# NSE2020_1.net
KiCad netlist of a schematic drawn in EAGLE
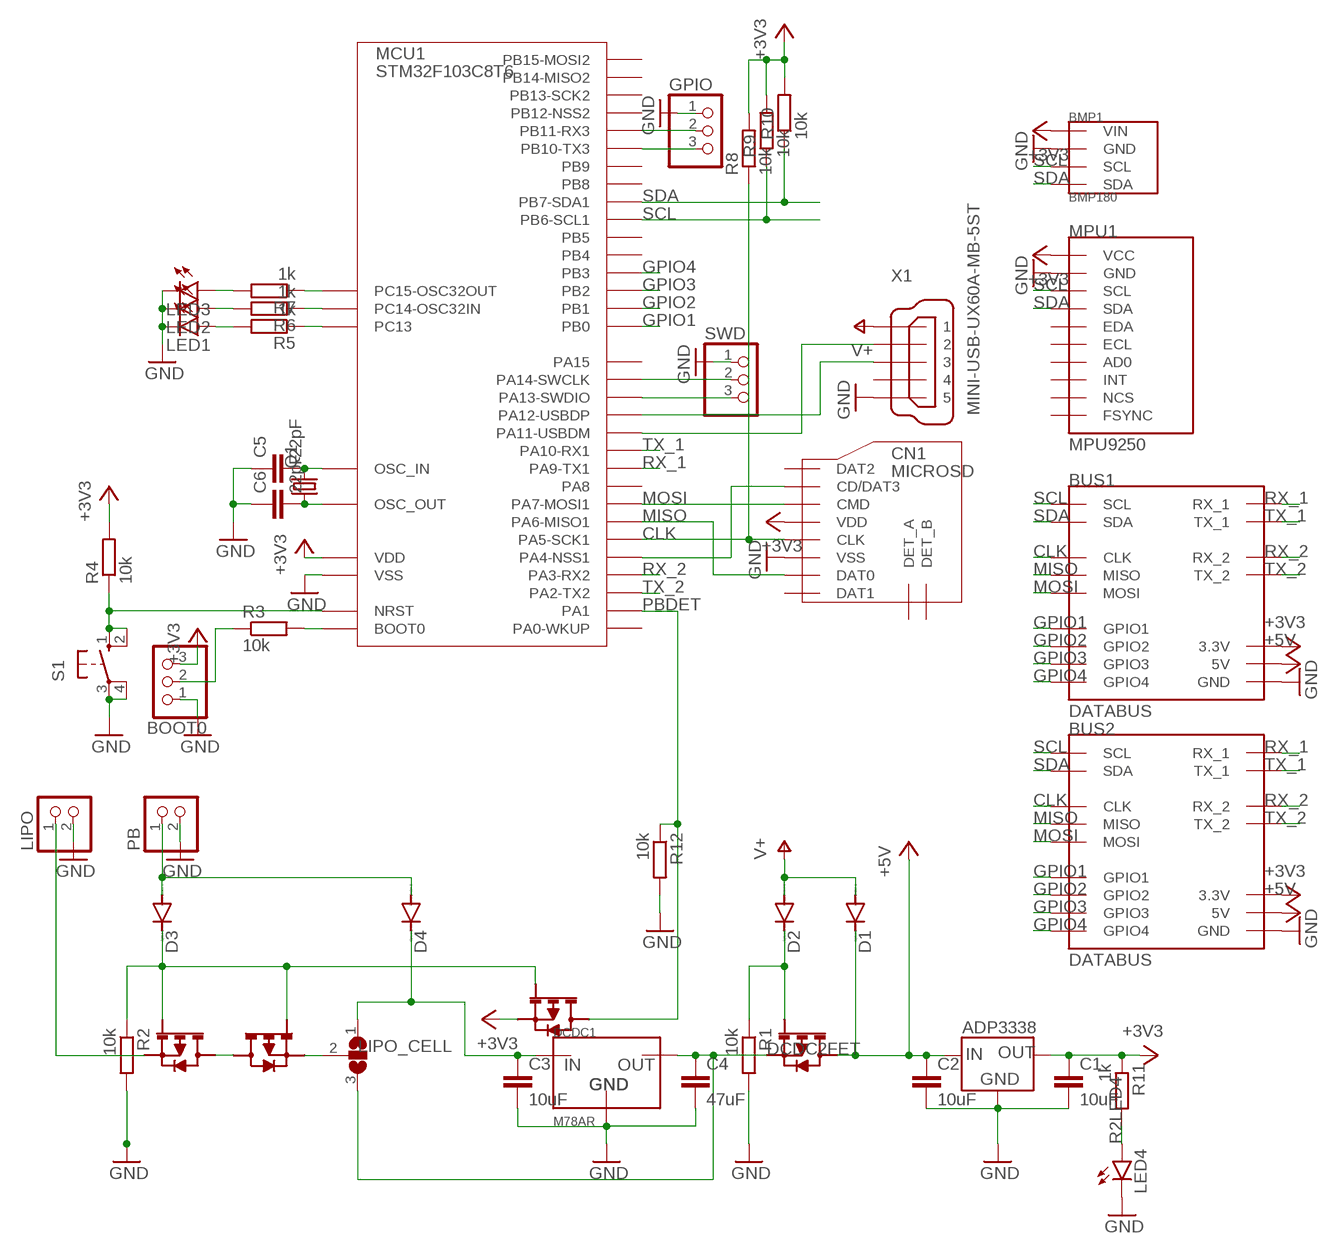
[diagram p0: schematic, sheet 1]

(export (version "E")
  (design (tool "Eeschema 10.0.6"))
  (components
    (comp (ref "BMP1")
      (value "BMP180")
      (footprint "eagle-import:GY-68")
      (libsource (lib "eagle-import") (part "BMP180"))
    )
    (comp (ref "BOOT0")
      (value "PINHD-1X3")
      (footprint "eagle-import:1X03")
      (libsource (lib "eagle-import") (part "PINHD-1X3"))
    )
    (comp (ref "BUS1")
      (value "DATABUS")
      (footprint "eagle-import:8X2")
      (libsource (lib "eagle-import") (part "DATABUS"))
    )
    (comp (ref "BUS2")
      (value "DATABUS")
      (footprint "eagle-import:8X2")
      (libsource (lib "eagle-import") (part "DATABUS"))
    )
    (comp (ref "C1")
      (value "10uF")
      (footprint "eagle-import:C2012")
      (libsource (lib "eagle-import") (part "C-EUC2012"))
    )
    (comp (ref "C2")
      (value "10uF")
      (footprint "eagle-import:C2012")
      (libsource (lib "eagle-import") (part "C-EUC2012"))
    )
    (comp (ref "C3")
      (value "10uF")
      (footprint "eagle-import:C2012")
      (libsource (lib "eagle-import") (part "C-EUC2012"))
    )
    (comp (ref "C4")
      (value "47uF")
      (footprint "eagle-import:C2012")
      (libsource (lib "eagle-import") (part "C-EUC2012"))
    )
    (comp (ref "C5")
      (value "22pF")
      (footprint "eagle-import:C2012")
      (libsource (lib "eagle-import") (part "C-EUC2012"))
    )
    (comp (ref "C6")
      (value "22pF")
      (footprint "eagle-import:C2012")
      (libsource (lib "eagle-import") (part "C-EUC2012"))
    )
    (comp (ref "CN1")
      (value "MICROSD")
      (footprint "eagle-import:DM3AT")
      (libsource (lib "eagle-import") (part "MICROSD"))
    )
    (comp (ref "D1")
      (value "DIODE-SOD123")
      (footprint "eagle-import:SOD123")
      (libsource (lib "eagle-import") (part "DIODE-SOD123"))
    )
    (comp (ref "D2")
      (value "DIODE-SOD123")
      (footprint "eagle-import:SOD123")
      (libsource (lib "eagle-import") (part "DIODE-SOD123"))
    )
    (comp (ref "D3")
      (value "DIODE-SOD123")
      (footprint "eagle-import:SOD123")
      (libsource (lib "eagle-import") (part "DIODE-SOD123"))
    )
    (comp (ref "D4")
      (value "DIODE-SOD123")
      (footprint "eagle-import:SOD123")
      (libsource (lib "eagle-import") (part "DIODE-SOD123"))
    )
    (comp (ref "DCDC1")
      (value "M78AR")
      (footprint "eagle-import:M78AR")
      (libsource (lib "eagle-import") (part "M78AR"))
    )
    (comp (ref "GPIO")
      (value "PINHD-1X3")
      (footprint "eagle-import:1X03")
      (libsource (lib "eagle-import") (part "PINHD-1X3"))
    )
    (comp (ref "IC1")
      (value "ADP3338-3.3")
      (footprint "eagle-import:SOT-223")
      (libsource (lib "eagle-import") (part "ADP3338-3.3"))
    )
    (comp (ref "LED1")
      (value "LEDSMT1206")
      (footprint "eagle-import:1206")
      (libsource (lib "eagle-import") (part "LEDSMT1206"))
    )
    (comp (ref "LED2")
      (value "LEDSMT1206")
      (footprint "eagle-import:1206")
      (libsource (lib "eagle-import") (part "LEDSMT1206"))
    )
    (comp (ref "LED3")
      (value "LEDSMT1206")
      (footprint "eagle-import:1206")
      (libsource (lib "eagle-import") (part "LEDSMT1206"))
    )
    (comp (ref "LED4")
      (value "LEDSMT1206")
      (footprint "eagle-import:1206")
      (libsource (lib "eagle-import") (part "LEDSMT1206"))
    )
    (comp (ref "LIPO")
      (value "PINHD-1X2")
      (footprint "eagle-import:1X02")
      (libsource (lib "eagle-import") (part "PINHD-1X2"))
    )
    (comp (ref "LIPO_CELL")
      (value "SJ2W")
      (footprint "eagle-import:SJ_2")
      (libsource (lib "eagle-import") (part "SJ2W"))
    )
    (comp (ref "MCU1")
      (value "STM32F103C8T6")
      (footprint "eagle-import:LQFP48")
      (libsource (lib "eagle-import") (part "STM32F103C8T6"))
    )
    (comp (ref "MPU1")
      (value "MPU9250")
      (footprint "eagle-import:GY-9250")
      (libsource (lib "eagle-import") (part "MPU9250"))
    )
    (comp (ref "PB")
      (value "PINHD-1X2")
      (footprint "eagle-import:1X02")
      (libsource (lib "eagle-import") (part "PINHD-1X2"))
    )
    (comp (ref "Q1")
      (value "CRYSTALHC49S")
      (footprint "eagle-import:HC49_S")
      (libsource (lib "eagle-import") (part "CRYSTALHC49S"))
    )
    (comp (ref "R1")
      (value "10k")
      (footprint "eagle-import:M2012")
      (libsource (lib "eagle-import") (part "R-EU_M2012"))
    )
    (comp (ref "R2")
      (value "10k")
      (footprint "eagle-import:M2012")
      (libsource (lib "eagle-import") (part "R-EU_M2012"))
    )
    (comp (ref "R3")
      (value "10k")
      (footprint "eagle-import:M2012")
      (libsource (lib "eagle-import") (part "R-EU_M2012"))
    )
    (comp (ref "R4")
      (value "10k")
      (footprint "eagle-import:M2012")
      (libsource (lib "eagle-import") (part "R-EU_M2012"))
    )
    (comp (ref "R5")
      (value "1k")
      (footprint "eagle-import:M2012")
      (libsource (lib "eagle-import") (part "R-EU_M2012"))
    )
    (comp (ref "R6")
      (value "1k")
      (footprint "eagle-import:M2012")
      (libsource (lib "eagle-import") (part "R-EU_M2012"))
    )
    (comp (ref "R7")
      (value "1k")
      (footprint "eagle-import:M2012")
      (libsource (lib "eagle-import") (part "R-EU_M2012"))
    )
    (comp (ref "R8")
      (value "10k")
      (footprint "eagle-import:M2012")
      (libsource (lib "eagle-import") (part "R-EU_M2012"))
    )
    (comp (ref "R9")
      (value "10k")
      (footprint "eagle-import:M2012")
      (libsource (lib "eagle-import") (part "R-EU_M2012"))
    )
    (comp (ref "R10")
      (value "10k")
      (footprint "eagle-import:M2012")
      (libsource (lib "eagle-import") (part "R-EU_M2012"))
    )
    (comp (ref "R11")
      (value "1k")
      (footprint "eagle-import:M2012")
      (libsource (lib "eagle-import") (part "R-EU_M2012"))
    )
    (comp (ref "R12")
      (value "10k")
      (footprint "eagle-import:M2012")
      (libsource (lib "eagle-import") (part "R-EU_M2012"))
    )
    (comp (ref "S1")
      (value "10-XX")
      (footprint "eagle-import:B3F-10XX")
      (fields (field (name "MPN") "B3F-1000"))
      (libsource (lib "eagle-import") (part "10-XX"))
    )
    (comp (ref "SWD")
      (value "PINHD-1X3")
      (footprint "eagle-import:1X03")
      (libsource (lib "eagle-import") (part "PINHD-1X3"))
    )
    (comp (ref "U$1")
      (value "2SJ681")
      (footprint "eagle-import:2SJ681")
      (libsource (lib "eagle-import") (part "2SJ681"))
    )
    (comp (ref "U$2")
      (value "2SJ681")
      (footprint "eagle-import:2SJ681")
      (libsource (lib "eagle-import") (part "2SJ681"))
    )
    (comp (ref "U$3")
      (value "2SJ681")
      (footprint "eagle-import:2SJ681")
      (libsource (lib "eagle-import") (part "2SJ681"))
    )
    (comp (ref "U$4")
      (value "2SJ681")
      (footprint "eagle-import:2SJ681")
      (libsource (lib "eagle-import") (part "2SJ681"))
    )
    (comp (ref "X1")
      (value "MINI-USB-UX60A-MB-5ST")
      (footprint "eagle-import:UX60A-MB-5ST")
      (libsource (lib "eagle-import") (part "MINI-USB-UX60A-MB-5ST"))
    )
  )
  (nets
    (net (code "1") (name "+3V3") (class "Default")
      (node (ref "BMP1") (pin "P1") (pinfunction "VIN_P1") (pintype "bidirectional"))
      (node (ref "BOOT0") (pin "3") (pinfunction "3_3") (pintype "passive"))
      (node (ref "BUS1") (pin "P6") (pinfunction "3.3V_P6") (pintype "bidirectional"))
      (node (ref "BUS2") (pin "P6") (pinfunction "3.3V_P6") (pintype "bidirectional"))
      (node (ref "C1") (pin "1") (pinfunction "1_1") (pintype "passive"))
      (node (ref "CN1") (pin "VDD") (pinfunction "VDD_VDD") (pintype "bidirectional"))
      (node (ref "IC1") (pin "1") (pinfunction "OUT_1") (pintype "output"))
      (node (ref "IC1") (pin "2") (pinfunction "OUT_2") (pintype "output"))
      (node (ref "MCU1") (pin "1") (pinfunction "VDD_1") (pintype "bidirectional"))
      (node (ref "MCU1") (pin "24") (pinfunction "VDD_24") (pintype "bidirectional"))
      (node (ref "MCU1") (pin "36") (pinfunction "VDD_36") (pintype "bidirectional"))
      (node (ref "MCU1") (pin "48") (pinfunction "VDD_48") (pintype "bidirectional"))
      (node (ref "MCU1") (pin "9") (pinfunction "VDD_9") (pintype "bidirectional"))
      (node (ref "MPU1") (pin "P1") (pinfunction "VCC_P1") (pintype "bidirectional"))
      (node (ref "R10") (pin "2") (pinfunction "2_2") (pintype "passive"))
      (node (ref "R11") (pin "1") (pinfunction "1_1") (pintype "passive"))
      (node (ref "R4") (pin "2") (pinfunction "2_2") (pintype "passive"))
      (node (ref "R8") (pin "2") (pinfunction "2_2") (pintype "passive"))
      (node (ref "R9") (pin "2") (pinfunction "2_2") (pintype "passive"))
      (node (ref "U$4") (pin "P$3") (pinfunction "P$3_P$3") (pintype "bidirectional"))
    )
    (net (code "2") (name "+5V") (class "Default")
      (node (ref "BUS1") (pin "P7") (pinfunction "5V_P7") (pintype "bidirectional"))
      (node (ref "BUS2") (pin "P7") (pinfunction "5V_P7") (pintype "bidirectional"))
      (node (ref "C2") (pin "1") (pinfunction "1_1") (pintype "passive"))
      (node (ref "D1") (pin "C") (pinfunction "C_C") (pintype "passive"))
      (node (ref "IC1") (pin "3") (pinfunction "IN_3") (pintype "input"))
      (node (ref "U$1") (pin "P$2") (pinfunction "P$1_P$2") (pintype "bidirectional"))
      (node (ref "U$1") (pin "P$4") (pinfunction "P$1_P$4") (pintype "bidirectional"))
    )
    (net (code "3") (name "/CLK") (class "Default")
      (node (ref "BUS1") (pin "P1") (pinfunction "CLK_P1") (pintype "bidirectional"))
      (node (ref "BUS2") (pin "P1") (pinfunction "CLK_P1") (pintype "bidirectional"))
      (node (ref "CN1") (pin "CLK") (pinfunction "CLK_CLK") (pintype "bidirectional"))
      (node (ref "MCU1") (pin "15") (pinfunction "PA5-SCK1_15") (pintype "bidirectional"))
      (node (ref "R8") (pin "1") (pinfunction "1_1") (pintype "passive"))
    )
    (net (code "4") (name "/DCDC2FET") (class "Default")
      (node (ref "C4") (pin "1") (pinfunction "1_1") (pintype "passive"))
      (node (ref "DCDC1") (pin "P3") (pinfunction "OUT_P3") (pintype "bidirectional"))
      (node (ref "LIPO_CELL") (pin "3") (pinfunction "3_3") (pintype "passive"))
      (node (ref "U$1") (pin "P$3") (pinfunction "P$3_P$3") (pintype "bidirectional"))
    )
    (net (code "5") (name "/GPIO1") (class "Default")
      (node (ref "BUS1") (pin "P3") (pinfunction "GPIO1_P3") (pintype "bidirectional"))
      (node (ref "BUS2") (pin "P3") (pinfunction "GPIO1_P3") (pintype "bidirectional"))
      (node (ref "MCU1") (pin "18") (pinfunction "PB0_18") (pintype "bidirectional"))
    )
    (net (code "6") (name "/GPIO2") (class "Default")
      (node (ref "BUS1") (pin "P10") (pinfunction "GPIO2_P10") (pintype "bidirectional"))
      (node (ref "BUS2") (pin "P10") (pinfunction "GPIO2_P10") (pintype "bidirectional"))
      (node (ref "MCU1") (pin "19") (pinfunction "PB1_19") (pintype "bidirectional"))
    )
    (net (code "7") (name "/GPIO3") (class "Default")
      (node (ref "BUS1") (pin "P14") (pinfunction "GPIO3_P14") (pintype "bidirectional"))
      (node (ref "BUS2") (pin "P14") (pinfunction "GPIO3_P14") (pintype "bidirectional"))
      (node (ref "MCU1") (pin "20") (pinfunction "PB2_20") (pintype "bidirectional"))
    )
    (net (code "8") (name "/GPIO4") (class "Default")
      (node (ref "BUS1") (pin "P15") (pinfunction "GPIO4_P15") (pintype "bidirectional"))
      (node (ref "BUS2") (pin "P15") (pinfunction "GPIO4_P15") (pintype "bidirectional"))
      (node (ref "MCU1") (pin "39") (pinfunction "PB3_39") (pintype "bidirectional"))
    )
    (net (code "9") (name "/MISO") (class "Default")
      (node (ref "BUS1") (pin "P12") (pinfunction "MISO_P12") (pintype "bidirectional"))
      (node (ref "BUS2") (pin "P12") (pinfunction "MISO_P12") (pintype "bidirectional"))
      (node (ref "CN1") (pin "DAT0") (pinfunction "DAT0_DAT0") (pintype "bidirectional"))
      (node (ref "MCU1") (pin "16") (pinfunction "PA6-MISO1_16") (pintype "bidirectional"))
    )
    (net (code "10") (name "/MOSI") (class "Default")
      (node (ref "BUS1") (pin "P2") (pinfunction "MOSI_P2") (pintype "bidirectional"))
      (node (ref "BUS2") (pin "P2") (pinfunction "MOSI_P2") (pintype "bidirectional"))
      (node (ref "CN1") (pin "CMD") (pinfunction "CMD_CMD") (pintype "bidirectional"))
      (node (ref "MCU1") (pin "17") (pinfunction "PA7-MOSI1_17") (pintype "bidirectional"))
    )
    (net (code "11") (name "/PBDET") (class "Default")
      (node (ref "MCU1") (pin "11") (pinfunction "PA1_11") (pintype "bidirectional"))
      (node (ref "R12") (pin "1") (pinfunction "1_1") (pintype "passive"))
      (node (ref "U$4") (pin "P$2") (pinfunction "P$1_P$2") (pintype "bidirectional"))
      (node (ref "U$4") (pin "P$4") (pinfunction "P$1_P$4") (pintype "bidirectional"))
    )
    (net (code "12") (name "/R2LED4") (class "Default")
      (node (ref "LED4") (pin "A") (pinfunction "A_A") (pintype "passive"))
      (node (ref "R11") (pin "2") (pinfunction "2_2") (pintype "passive"))
    )
    (net (code "13") (name "/RX_1") (class "Default")
      (node (ref "BUS1") (pin "P4") (pinfunction "RX_1_P4") (pintype "bidirectional"))
      (node (ref "BUS2") (pin "P4") (pinfunction "RX_1_P4") (pintype "bidirectional"))
      (node (ref "MCU1") (pin "30") (pinfunction "PA9-TX1_30") (pintype "bidirectional"))
    )
    (net (code "14") (name "/RX_2") (class "Default")
      (node (ref "BUS1") (pin "P9") (pinfunction "RX_2_P9") (pintype "bidirectional"))
      (node (ref "BUS2") (pin "P9") (pinfunction "RX_2_P9") (pintype "bidirectional"))
      (node (ref "MCU1") (pin "13") (pinfunction "PA3-RX2_13") (pintype "bidirectional"))
    )
    (net (code "15") (name "/SCL") (class "Default")
      (node (ref "BMP1") (pin "P3") (pinfunction "SCL_P3") (pintype "bidirectional"))
      (node (ref "BUS1") (pin "P0") (pinfunction "SCL_P0") (pintype "bidirectional"))
      (node (ref "BUS2") (pin "P0") (pinfunction "SCL_P0") (pintype "bidirectional"))
      (node (ref "MCU1") (pin "42") (pinfunction "PB6-SCL1_42") (pintype "bidirectional"))
      (node (ref "MPU1") (pin "P3") (pinfunction "SCL_P3") (pintype "bidirectional"))
      (node (ref "R9") (pin "1") (pinfunction "1_1") (pintype "passive"))
    )
    (net (code "16") (name "/SDA") (class "Default")
      (node (ref "BMP1") (pin "P4") (pinfunction "SDA_P4") (pintype "bidirectional"))
      (node (ref "BUS1") (pin "P13") (pinfunction "SDA_P13") (pintype "bidirectional"))
      (node (ref "BUS2") (pin "P13") (pinfunction "SDA_P13") (pintype "bidirectional"))
      (node (ref "MCU1") (pin "43") (pinfunction "PB7-SDA1_43") (pintype "bidirectional"))
      (node (ref "MPU1") (pin "P4") (pinfunction "SDA_P4") (pintype "bidirectional"))
      (node (ref "R10") (pin "1") (pinfunction "1_1") (pintype "passive"))
    )
    (net (code "17") (name "/TX_1") (class "Default")
      (node (ref "BUS1") (pin "P5") (pinfunction "TX_1_P5") (pintype "bidirectional"))
      (node (ref "BUS2") (pin "P5") (pinfunction "TX_1_P5") (pintype "bidirectional"))
      (node (ref "MCU1") (pin "31") (pinfunction "PA10-RX1_31") (pintype "bidirectional"))
    )
    (net (code "18") (name "/TX_2") (class "Default")
      (node (ref "BUS1") (pin "P8") (pinfunction "TX_2_P8") (pintype "bidirectional"))
      (node (ref "BUS2") (pin "P8") (pinfunction "TX_2_P8") (pintype "bidirectional"))
      (node (ref "MCU1") (pin "12") (pinfunction "PA2-TX2_12") (pintype "bidirectional"))
    )
    (net (code "19") (name "GND") (class "Default")
      (node (ref "BMP1") (pin "P2") (pinfunction "GND_P2") (pintype "bidirectional"))
      (node (ref "BOOT0") (pin "1") (pinfunction "1_1") (pintype "passive"))
      (node (ref "BUS1") (pin "P11") (pinfunction "GND_P11") (pintype "bidirectional"))
      (node (ref "BUS2") (pin "P11") (pinfunction "GND_P11") (pintype "bidirectional"))
      (node (ref "C1") (pin "2") (pinfunction "2_2") (pintype "passive"))
      (node (ref "C2") (pin "2") (pinfunction "2_2") (pintype "passive"))
      (node (ref "C3") (pin "2") (pinfunction "2_2") (pintype "passive"))
      (node (ref "C4") (pin "2") (pinfunction "2_2") (pintype "passive"))
      (node (ref "C5") (pin "1") (pinfunction "1_1") (pintype "passive"))
      (node (ref "C6") (pin "1") (pinfunction "1_1") (pintype "passive"))
      (node (ref "CN1") (pin "VSS") (pinfunction "VSS_VSS") (pintype "bidirectional"))
      (node (ref "DCDC1") (pin "P2") (pinfunction "GND_P2") (pintype "bidirectional"))
      (node (ref "GPIO") (pin "1") (pinfunction "1_1") (pintype "passive"))
      (node (ref "IC1") (pin "4") (pinfunction "GND_4") (pintype "bidirectional"))
      (node (ref "LED1") (pin "C") (pinfunction "C_C") (pintype "passive"))
      (node (ref "LED2") (pin "C") (pinfunction "C_C") (pintype "passive"))
      (node (ref "LED3") (pin "C") (pinfunction "C_C") (pintype "passive"))
      (node (ref "LED4") (pin "C") (pinfunction "C_C") (pintype "passive"))
      (node (ref "LIPO") (pin "2") (pinfunction "2_2") (pintype "passive"))
      (node (ref "MCU1") (pin "23") (pinfunction "VSS_23") (pintype "bidirectional"))
      (node (ref "MCU1") (pin "35") (pinfunction "VSS_35") (pintype "bidirectional"))
      (node (ref "MCU1") (pin "47") (pinfunction "VSS_47") (pintype "bidirectional"))
      (node (ref "MCU1") (pin "8") (pinfunction "VSS_8") (pintype "bidirectional"))
      (node (ref "MPU1") (pin "P10") (pinfunction "GND_P10") (pintype "bidirectional"))
      (node (ref "PB") (pin "2") (pinfunction "2_2") (pintype "passive"))
      (node (ref "R1") (pin "2") (pinfunction "2_2") (pintype "passive"))
      (node (ref "R12") (pin "2") (pinfunction "2_2") (pintype "passive"))
      (node (ref "R2") (pin "2") (pinfunction "2_2") (pintype "passive"))
      (node (ref "S1") (pin "3") (pinfunction "P_3") (pintype "passive"))
      (node (ref "S1") (pin "4") (pinfunction "P1_4") (pintype "passive"))
      (node (ref "SWD") (pin "1") (pinfunction "1_1") (pintype "passive"))
      (node (ref "X1") (pin "5") (pinfunction "5_5") (pintype "input"))
    )
    (net (code "20") (name "Net-(BOOT0-Pad2)") (class "Default")
      (node (ref "BOOT0") (pin "2") (pinfunction "2_2") (pintype "passive"))
      (node (ref "R3") (pin "1") (pinfunction "1_1") (pintype "passive"))
    )
    (net (code "21") (name "Net-(D3-PadA)") (class "Default")
      (node (ref "D3") (pin "A") (pinfunction "A_A") (pintype "passive"))
      (node (ref "D4") (pin "A") (pinfunction "A_A") (pintype "passive"))
      (node (ref "PB") (pin "1") (pinfunction "1_1") (pintype "passive"))
    )
    (net (code "22") (name "Net-(DCDC1-IN)") (class "Default")
      (node (ref "C3") (pin "1") (pinfunction "1_1") (pintype "passive"))
      (node (ref "D4") (pin "C") (pinfunction "C_C") (pintype "passive"))
      (node (ref "DCDC1") (pin "P1") (pinfunction "IN_P1") (pintype "bidirectional"))
      (node (ref "LIPO_CELL") (pin "1") (pinfunction "1_1") (pintype "passive"))
    )
    (net (code "23") (name "Net-(LED1-PadA)") (class "Default")
      (node (ref "LED1") (pin "A") (pinfunction "A_A") (pintype "passive"))
      (node (ref "R5") (pin "2") (pinfunction "2_2") (pintype "passive"))
    )
    (net (code "24") (name "Net-(LED2-PadA)") (class "Default")
      (node (ref "LED2") (pin "A") (pinfunction "A_A") (pintype "passive"))
      (node (ref "R6") (pin "2") (pinfunction "2_2") (pintype "passive"))
    )
    (net (code "25") (name "Net-(LED3-PadA)") (class "Default")
      (node (ref "LED3") (pin "A") (pinfunction "A_A") (pintype "passive"))
      (node (ref "R7") (pin "2") (pinfunction "2_2") (pintype "passive"))
    )
    (net (code "26") (name "Net-(LIPO-Pad1)") (class "Default")
      (node (ref "LIPO") (pin "1") (pinfunction "1_1") (pintype "passive"))
      (node (ref "U$3") (pin "P$3") (pinfunction "P$3_P$3") (pintype "bidirectional"))
    )
    (net (code "27") (name "Net-(LIPO_CELL-Pad2)") (class "Default")
      (node (ref "LIPO_CELL") (pin "2") (pinfunction "2_2") (pintype "passive"))
      (node (ref "U$2") (pin "P$3") (pinfunction "P$3_P$3") (pintype "bidirectional"))
    )
    (net (code "28") (name "Net-(MCU1-BOOT0)") (class "Default")
      (node (ref "MCU1") (pin "44") (pinfunction "BOOT0_44") (pintype "bidirectional"))
      (node (ref "R3") (pin "2") (pinfunction "2_2") (pintype "passive"))
    )
    (net (code "29") (name "Net-(MCU1-NRST)") (class "Default")
      (node (ref "MCU1") (pin "7") (pinfunction "NRST_7") (pintype "bidirectional"))
      (node (ref "R4") (pin "1") (pinfunction "1_1") (pintype "passive"))
      (node (ref "S1") (pin "1") (pinfunction "S_1") (pintype "passive"))
      (node (ref "S1") (pin "2") (pinfunction "S1_2") (pintype "passive"))
    )
    (net (code "30") (name "Net-(MCU1-OSC_IN)") (class "Default")
      (node (ref "C5") (pin "2") (pinfunction "2_2") (pintype "passive"))
      (node (ref "MCU1") (pin "5") (pinfunction "OSC_IN_5") (pintype "bidirectional"))
      (node (ref "Q1") (pin "2") (pinfunction "2_2") (pintype "passive"))
    )
    (net (code "31") (name "Net-(MCU1-OSC_OUT)") (class "Default")
      (node (ref "C6") (pin "2") (pinfunction "2_2") (pintype "passive"))
      (node (ref "MCU1") (pin "6") (pinfunction "OSC_OUT_6") (pintype "bidirectional"))
      (node (ref "Q1") (pin "1") (pinfunction "1_1") (pintype "passive"))
    )
    (net (code "32") (name "Net-(MCU1-PA4-NSS1)") (class "Default")
      (node (ref "CN1") (pin "CD/DAT3") (pinfunction "CD/DAT3_CD/DAT3") (pintype "bidirectional"))
      (node (ref "MCU1") (pin "14") (pinfunction "PA4-NSS1_14") (pintype "bidirectional"))
    )
    (net (code "33") (name "Net-(MCU1-PA11-USBDM)") (class "Default")
      (node (ref "MCU1") (pin "32") (pinfunction "PA11-USBDM_32") (pintype "bidirectional"))
      (node (ref "X1") (pin "2") (pinfunction "2_2") (pintype "input"))
    )
    (net (code "34") (name "Net-(MCU1-PA12-USBDP)") (class "Default")
      (node (ref "MCU1") (pin "33") (pinfunction "PA12-USBDP_33") (pintype "bidirectional"))
      (node (ref "X1") (pin "3") (pinfunction "3_3") (pintype "input"))
    )
    (net (code "35") (name "Net-(MCU1-PA13-SWDIO)") (class "Default")
      (node (ref "MCU1") (pin "34") (pinfunction "PA13-SWDIO_34") (pintype "bidirectional"))
      (node (ref "SWD") (pin "3") (pinfunction "3_3") (pintype "passive"))
    )
    (net (code "36") (name "Net-(MCU1-PA14-SWCLK)") (class "Default")
      (node (ref "MCU1") (pin "37") (pinfunction "PA14-SWCLK_37") (pintype "bidirectional"))
      (node (ref "SWD") (pin "2") (pinfunction "2_2") (pintype "passive"))
    )
    (net (code "37") (name "Net-(MCU1-PB10-TX3)") (class "Default")
      (node (ref "GPIO") (pin "3") (pinfunction "3_3") (pintype "passive"))
      (node (ref "MCU1") (pin "21") (pinfunction "PB10-TX3_21") (pintype "bidirectional"))
    )
    (net (code "38") (name "Net-(MCU1-PB11-RX3)") (class "Default")
      (node (ref "GPIO") (pin "2") (pinfunction "2_2") (pintype "passive"))
      (node (ref "MCU1") (pin "22") (pinfunction "PB11-RX3_22") (pintype "bidirectional"))
    )
    (net (code "39") (name "Net-(MCU1-PC13)") (class "Default")
      (node (ref "MCU1") (pin "2") (pinfunction "PC13_2") (pintype "bidirectional"))
      (node (ref "R5") (pin "1") (pinfunction "1_1") (pintype "passive"))
    )
    (net (code "40") (name "Net-(MCU1-PC14-OSC32IN)") (class "Default")
      (node (ref "MCU1") (pin "3") (pinfunction "PC14-OSC32IN_3") (pintype "bidirectional"))
      (node (ref "R6") (pin "1") (pinfunction "1_1") (pintype "passive"))
    )
    (net (code "41") (name "Net-(MCU1-PC15-OSC32OUT)") (class "Default")
      (node (ref "MCU1") (pin "4") (pinfunction "PC15-OSC32OUT_4") (pintype "bidirectional"))
      (node (ref "R7") (pin "1") (pinfunction "1_1") (pintype "passive"))
    )
    (net (code "42") (name "Net-(U$1-P$2)") (class "Default")
      (node (ref "D2") (pin "C") (pinfunction "C_C") (pintype "passive"))
      (node (ref "R1") (pin "1") (pinfunction "1_1") (pintype "passive"))
      (node (ref "U$1") (pin "P$1") (pinfunction "P$2_P$1") (pintype "bidirectional"))
    )
    (net (code "43") (name "Net-(U$2-P$1-PadP$2)") (class "Default")
      (node (ref "U$2") (pin "P$2") (pinfunction "P$1_P$2") (pintype "bidirectional"))
      (node (ref "U$2") (pin "P$4") (pinfunction "P$1_P$4") (pintype "bidirectional"))
      (node (ref "U$3") (pin "P$2") (pinfunction "P$1_P$2") (pintype "bidirectional"))
      (node (ref "U$3") (pin "P$4") (pinfunction "P$1_P$4") (pintype "bidirectional"))
    )
    (net (code "44") (name "Net-(U$2-P$2)") (class "Default")
      (node (ref "D3") (pin "C") (pinfunction "C_C") (pintype "passive"))
      (node (ref "R2") (pin "1") (pinfunction "1_1") (pintype "passive"))
      (node (ref "U$2") (pin "P$1") (pinfunction "P$2_P$1") (pintype "bidirectional"))
      (node (ref "U$3") (pin "P$1") (pinfunction "P$2_P$1") (pintype "bidirectional"))
      (node (ref "U$4") (pin "P$1") (pinfunction "P$2_P$1") (pintype "bidirectional"))
    )
    (net (code "45") (name "V+") (class "Default")
      (node (ref "D1") (pin "A") (pinfunction "A_A") (pintype "passive"))
      (node (ref "D2") (pin "A") (pinfunction "A_A") (pintype "passive"))
      (node (ref "X1") (pin "1") (pinfunction "1_1") (pintype "input"))
    )
    (net (code "46") (name "unconnected-(CN1-PadDAT1)") (class "Default")
      (node (ref "CN1") (pin "DAT1") (pinfunction "DAT1_DAT1") (pintype "bidirectional"))
    )
    (net (code "47") (name "unconnected-(CN1-PadDAT2)") (class "Default")
      (node (ref "CN1") (pin "DAT2") (pinfunction "DAT2_DAT2") (pintype "bidirectional"))
    )
    (net (code "48") (name "unconnected-(CN1-PadDET_A)") (class "Default")
      (node (ref "CN1") (pin "DET_A") (pinfunction "DET_A_DET_A") (pintype "bidirectional"))
    )
    (net (code "49") (name "unconnected-(CN1-PadDET_B)") (class "Default")
      (node (ref "CN1") (pin "DET_B") (pinfunction "DET_B_DET_B") (pintype "bidirectional"))
    )
    (net (code "50") (name "unconnected-(MCU1-PA0-WKUP-Pad10)") (class "Default")
      (node (ref "MCU1") (pin "10") (pinfunction "PA0-WKUP_10") (pintype "bidirectional"))
    )
    (net (code "51") (name "unconnected-(MCU1-PA8-Pad29)") (class "Default")
      (node (ref "MCU1") (pin "29") (pinfunction "PA8_29") (pintype "bidirectional"))
    )
    (net (code "52") (name "unconnected-(MCU1-PA15-Pad38)") (class "Default")
      (node (ref "MCU1") (pin "38") (pinfunction "PA15_38") (pintype "bidirectional"))
    )
    (net (code "53") (name "unconnected-(MCU1-PB4-Pad40)") (class "Default")
      (node (ref "MCU1") (pin "40") (pinfunction "PB4_40") (pintype "bidirectional"))
    )
    (net (code "54") (name "unconnected-(MCU1-PB5-Pad41)") (class "Default")
      (node (ref "MCU1") (pin "41") (pinfunction "PB5_41") (pintype "bidirectional"))
    )
    (net (code "55") (name "unconnected-(MCU1-PB8-Pad45)") (class "Default")
      (node (ref "MCU1") (pin "45") (pinfunction "PB8_45") (pintype "bidirectional"))
    )
    (net (code "56") (name "unconnected-(MCU1-PB9-Pad46)") (class "Default")
      (node (ref "MCU1") (pin "46") (pinfunction "PB9_46") (pintype "bidirectional"))
    )
    (net (code "57") (name "unconnected-(MCU1-PB12-NSS2-Pad25)") (class "Default")
      (node (ref "MCU1") (pin "25") (pinfunction "PB12-NSS2_25") (pintype "bidirectional"))
    )
    (net (code "58") (name "unconnected-(MCU1-PB13-SCK2-Pad26)") (class "Default")
      (node (ref "MCU1") (pin "26") (pinfunction "PB13-SCK2_26") (pintype "bidirectional"))
    )
    (net (code "59") (name "unconnected-(MCU1-PB14-MISO2-Pad27)") (class "Default")
      (node (ref "MCU1") (pin "27") (pinfunction "PB14-MISO2_27") (pintype "bidirectional"))
    )
    (net (code "60") (name "unconnected-(MCU1-PB15-MOSI2-Pad28)") (class "Default")
      (node (ref "MCU1") (pin "28") (pinfunction "PB15-MOSI2_28") (pintype "bidirectional"))
    )
    (net (code "61") (name "unconnected-(MPU1-AD0-PadP2)") (class "Default")
      (node (ref "MPU1") (pin "P2") (pinfunction "AD0_P2") (pintype "bidirectional"))
    )
    (net (code "62") (name "unconnected-(MPU1-ECL-PadP5)") (class "Default")
      (node (ref "MPU1") (pin "P5") (pinfunction "ECL_P5") (pintype "bidirectional"))
    )
    (net (code "63") (name "unconnected-(MPU1-EDA-PadP6)") (class "Default")
      (node (ref "MPU1") (pin "P6") (pinfunction "EDA_P6") (pintype "bidirectional"))
    )
    (net (code "64") (name "unconnected-(MPU1-FSYNC-PadP7)") (class "Default")
      (node (ref "MPU1") (pin "P7") (pinfunction "FSYNC_P7") (pintype "bidirectional"))
    )
    (net (code "65") (name "unconnected-(MPU1-INT-PadP8)") (class "Default")
      (node (ref "MPU1") (pin "P8") (pinfunction "INT_P8") (pintype "bidirectional"))
    )
    (net (code "66") (name "unconnected-(MPU1-NCS-PadP9)") (class "Default")
      (node (ref "MPU1") (pin "P9") (pinfunction "NCS_P9") (pintype "bidirectional"))
    )
    (net (code "67") (name "unconnected-(X1-Pad4)") (class "Default")
      (node (ref "X1") (pin "4") (pinfunction "4_4") (pintype "input"))
    )
  )
)
